# Hyttkontakt.net
KiCad netlist of a schematic drawn in EAGLE
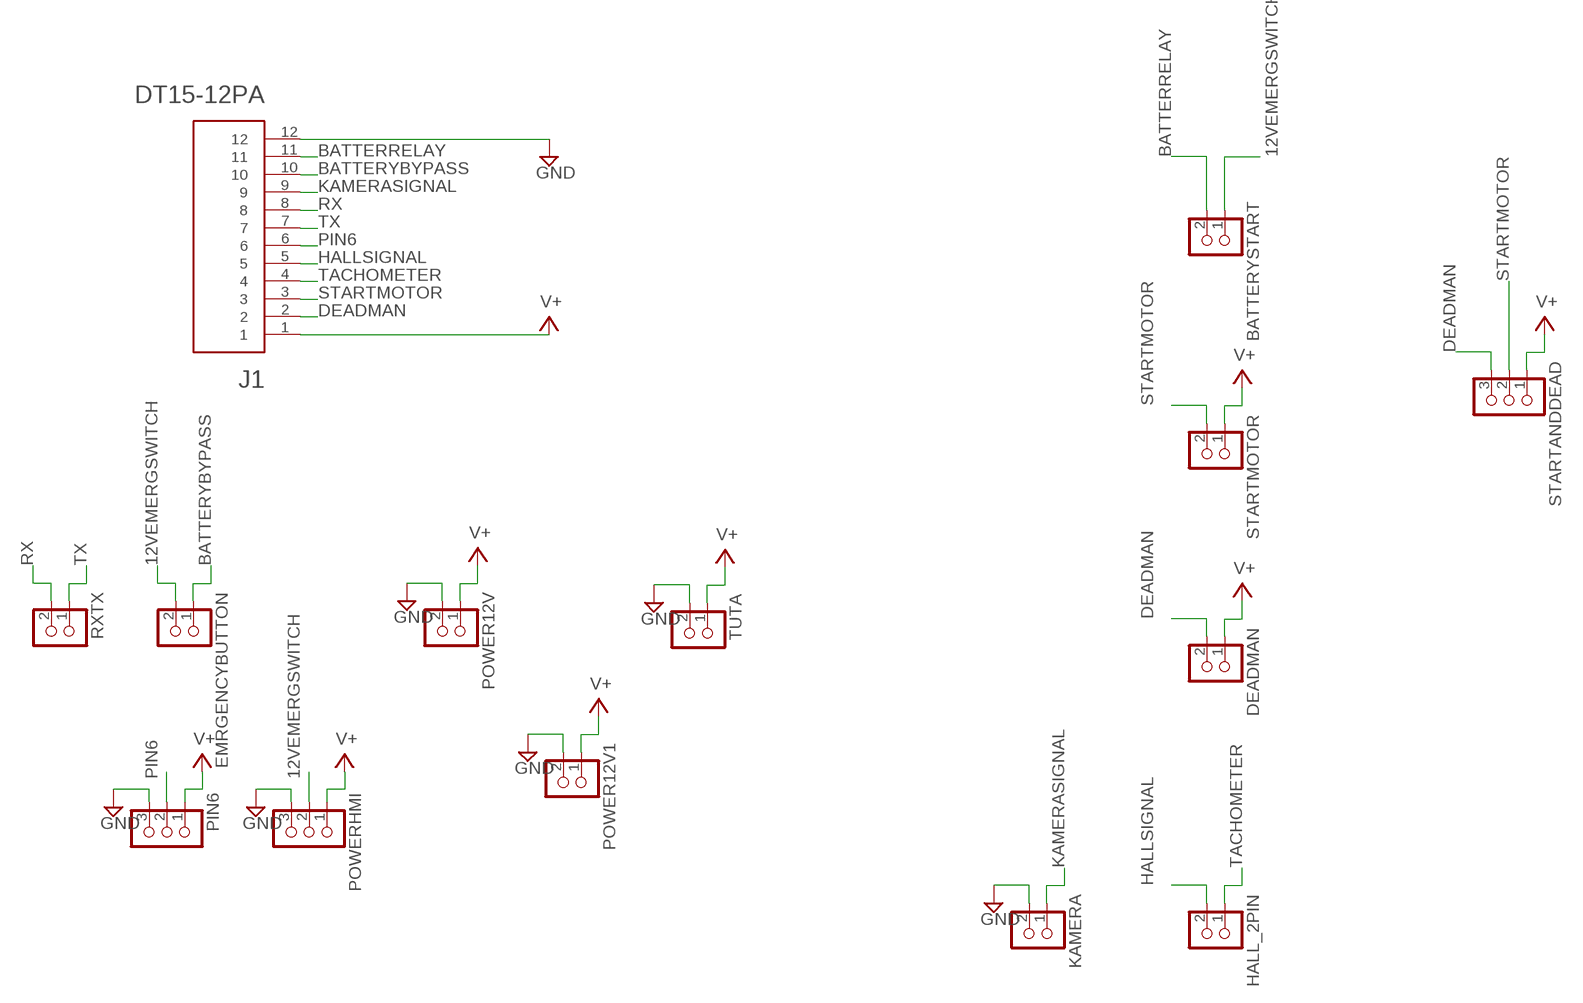
[diagram p0: schematic, sheet 1]

(export (version "E")
  (design (tool "Eeschema 10.0.6"))
  (components
    (comp (ref "BATTERYSTART")
      (value "EH_B2B-EH")
      (footprint "eagle-import:B2B-EH")
      (libsource (lib "eagle-import") (part "EH_B2B-EH"))
    )
    (comp (ref "DEADMAN")
      (value "EH_B2B-EH")
      (footprint "eagle-import:B2B-EH")
      (libsource (lib "eagle-import") (part "EH_B2B-EH"))
    )
    (comp (ref "EMRGENCYBUTTON")
      (value "EH_B2B-EH")
      (footprint "eagle-import:B2B-EH")
      (libsource (lib "eagle-import") (part "EH_B2B-EH"))
    )
    (comp (ref "HALL_2PIN")
      (value "EH_B2B-EH")
      (footprint "eagle-import:B2B-EH")
      (libsource (lib "eagle-import") (part "EH_B2B-EH"))
    )
    (comp (ref "J1")
      (value "DT15-12PA")
      (footprint "eagle-import:TE_DT15-12PA")
      (fields (field (name "MF") "TE Connectivity"))
      (libsource (lib "eagle-import") (part "DT15-12PA"))
    )
    (comp (ref "KAMERA")
      (value "EH_B2B-EH")
      (footprint "eagle-import:B2B-EH")
      (libsource (lib "eagle-import") (part "EH_B2B-EH"))
    )
    (comp (ref "PIN6")
      (value "EH_B3B-EH")
      (footprint "eagle-import:B3B-EH")
      (libsource (lib "eagle-import") (part "EH_B3B-EH"))
    )
    (comp (ref "POWER12V")
      (value "EH_B2B-EH")
      (footprint "eagle-import:B2B-EH")
      (libsource (lib "eagle-import") (part "EH_B2B-EH"))
    )
    (comp (ref "POWER12V1")
      (value "EH_B2B-EH")
      (footprint "eagle-import:B2B-EH")
      (libsource (lib "eagle-import") (part "EH_B2B-EH"))
    )
    (comp (ref "POWERHMI")
      (value "EH_B3B-EH")
      (footprint "eagle-import:B3B-EH")
      (libsource (lib "eagle-import") (part "EH_B3B-EH"))
    )
    (comp (ref "RXTX")
      (value "EH_B2B-EH")
      (footprint "eagle-import:B2B-EH")
      (libsource (lib "eagle-import") (part "EH_B2B-EH"))
    )
    (comp (ref "STARTANDDEAD")
      (value "EH_B3B-EH")
      (footprint "eagle-import:B3B-EH")
      (libsource (lib "eagle-import") (part "EH_B3B-EH"))
    )
    (comp (ref "STARTMOTOR")
      (value "EH_B2B-EH")
      (footprint "eagle-import:B2B-EH")
      (libsource (lib "eagle-import") (part "EH_B2B-EH"))
    )
    (comp (ref "TUTA")
      (value "EH_B2B-EH")
      (footprint "eagle-import:B2B-EH")
      (libsource (lib "eagle-import") (part "EH_B2B-EH"))
    )
  )
  (nets
    (net (code "1") (name "/12VEMERGSWITCH") (class "Default")
      (node (ref "BATTERYSTART") (pin "1") (pinfunction "1_1") (pintype "passive"))
      (node (ref "EMRGENCYBUTTON") (pin "2") (pinfunction "2_2") (pintype "passive"))
      (node (ref "POWERHMI") (pin "2") (pinfunction "2_2") (pintype "passive"))
    )
    (net (code "2") (name "/BATTERRELAY") (class "Default")
      (node (ref "BATTERYSTART") (pin "2") (pinfunction "2_2") (pintype "passive"))
      (node (ref "J1") (pin "11") (pinfunction "11_11") (pintype "passive"))
    )
    (net (code "3") (name "/BATTERYBYPASS") (class "Default")
      (node (ref "EMRGENCYBUTTON") (pin "1") (pinfunction "1_1") (pintype "passive"))
      (node (ref "J1") (pin "10") (pinfunction "10_10") (pintype "passive"))
    )
    (net (code "4") (name "/DEADMAN") (class "Default")
      (node (ref "DEADMAN") (pin "2") (pinfunction "2_2") (pintype "passive"))
      (node (ref "J1") (pin "2") (pinfunction "2_2") (pintype "passive"))
      (node (ref "STARTANDDEAD") (pin "3") (pinfunction "3_3") (pintype "passive"))
    )
    (net (code "5") (name "/HALLSIGNAL") (class "Default")
      (node (ref "HALL_2PIN") (pin "2") (pinfunction "2_2") (pintype "passive"))
      (node (ref "J1") (pin "5") (pinfunction "5_5") (pintype "passive"))
    )
    (net (code "6") (name "/KAMERASIGNAL") (class "Default")
      (node (ref "J1") (pin "9") (pinfunction "9_9") (pintype "passive"))
      (node (ref "KAMERA") (pin "1") (pinfunction "1_1") (pintype "passive"))
    )
    (net (code "7") (name "/PIN6") (class "Default")
      (node (ref "J1") (pin "6") (pinfunction "6_6") (pintype "passive"))
      (node (ref "PIN6") (pin "2") (pinfunction "2_2") (pintype "passive"))
    )
    (net (code "8") (name "/RX") (class "Default")
      (node (ref "J1") (pin "8") (pinfunction "8_8") (pintype "passive"))
      (node (ref "RXTX") (pin "2") (pinfunction "2_2") (pintype "passive"))
    )
    (net (code "9") (name "/STARTMOTOR") (class "Default")
      (node (ref "J1") (pin "3") (pinfunction "3_3") (pintype "passive"))
      (node (ref "STARTANDDEAD") (pin "2") (pinfunction "2_2") (pintype "passive"))
      (node (ref "STARTMOTOR") (pin "2") (pinfunction "2_2") (pintype "passive"))
    )
    (net (code "10") (name "/TACHOMETER") (class "Default")
      (node (ref "HALL_2PIN") (pin "1") (pinfunction "1_1") (pintype "passive"))
      (node (ref "J1") (pin "4") (pinfunction "4_4") (pintype "passive"))
    )
    (net (code "11") (name "/TX") (class "Default")
      (node (ref "J1") (pin "7") (pinfunction "7_7") (pintype "passive"))
      (node (ref "RXTX") (pin "1") (pinfunction "1_1") (pintype "passive"))
    )
    (net (code "12") (name "GND") (class "Default")
      (node (ref "J1") (pin "12") (pinfunction "12_12") (pintype "passive"))
      (node (ref "KAMERA") (pin "2") (pinfunction "2_2") (pintype "passive"))
      (node (ref "PIN6") (pin "3") (pinfunction "3_3") (pintype "passive"))
      (node (ref "POWER12V") (pin "2") (pinfunction "2_2") (pintype "passive"))
      (node (ref "POWER12V1") (pin "2") (pinfunction "2_2") (pintype "passive"))
      (node (ref "POWERHMI") (pin "3") (pinfunction "3_3") (pintype "passive"))
      (node (ref "TUTA") (pin "2") (pinfunction "2_2") (pintype "passive"))
    )
    (net (code "13") (name "V+") (class "Default")
      (node (ref "DEADMAN") (pin "1") (pinfunction "1_1") (pintype "passive"))
      (node (ref "J1") (pin "1") (pinfunction "1_1") (pintype "passive"))
      (node (ref "PIN6") (pin "1") (pinfunction "1_1") (pintype "passive"))
      (node (ref "POWER12V") (pin "1") (pinfunction "1_1") (pintype "passive"))
      (node (ref "POWER12V1") (pin "1") (pinfunction "1_1") (pintype "passive"))
      (node (ref "POWERHMI") (pin "1") (pinfunction "1_1") (pintype "passive"))
      (node (ref "STARTANDDEAD") (pin "1") (pinfunction "1_1") (pintype "passive"))
      (node (ref "STARTMOTOR") (pin "1") (pinfunction "1_1") (pintype "passive"))
      (node (ref "TUTA") (pin "1") (pinfunction "1_1") (pintype "passive"))
    )
  )
)
